# Amplifier_ADC.net
KiCad netlist of a schematic drawn in Altium Designer
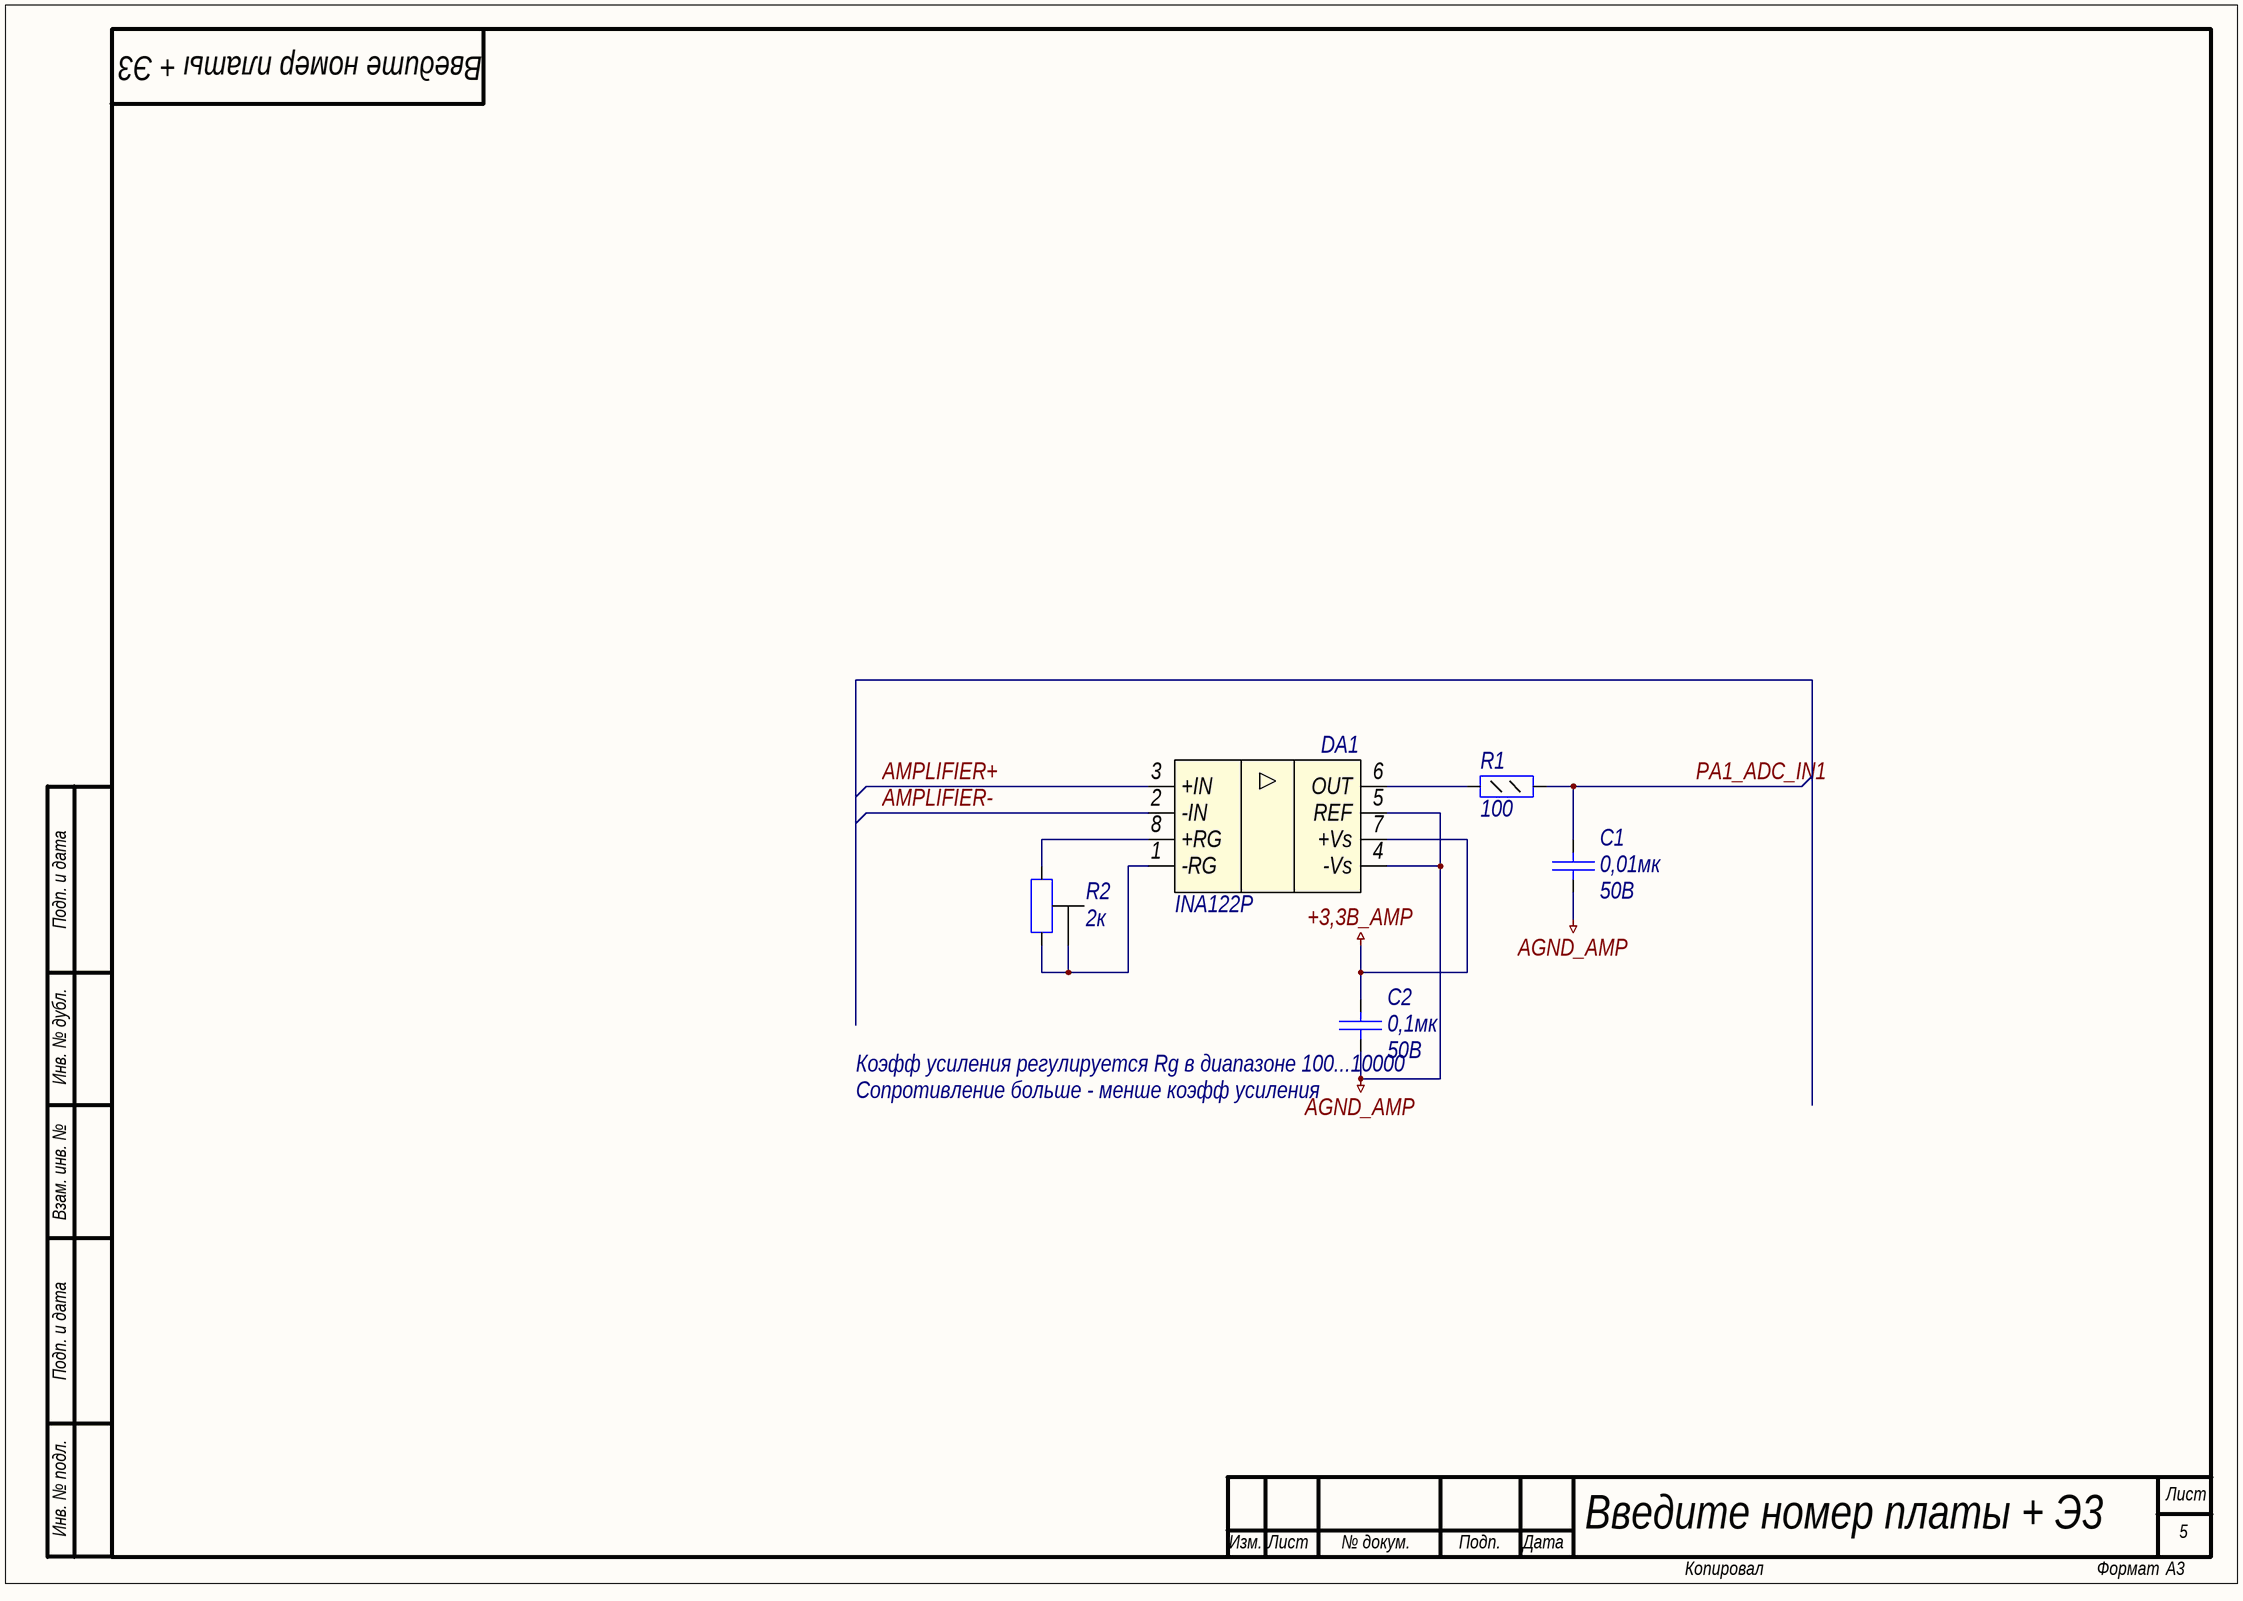
[diagram p0: Amplifier_ADC.SchDoc]

(export (version "E")
  (design (tool "Eeschema 10.0.6"))
  (components
    (comp (ref "C1")
      (value "0,01мк")
      (footprint "C0805")
      (description "Конденсатор")
      (fields
        (field (name "VOLTAGE") "50B")
        (field (name "PART NUMBER") "GRM216R71H103K")
        (field (name "Comment") "Capacitor")
      )
      (libsource (lib "MOP44") (part "Capacitor"))
    )
    (comp (ref "C2")
      (value "0,1мк")
      (footprint "C0805")
      (description "Конденсатор")
      (fields
        (field (name "VOLTAGE") "50В")
        (field (name "PART NUMBER") "GRM21BR71H104KA01L ")
        (field (name "Comment") "Capacitor")
      )
      (libsource (lib "MOP44") (part "Capacitor"))
    )
    (comp (ref "DA1")
      (value "INA122")
      (footprint "DIP8")
      (description "Low Cost Low Power  Instrumentation Amplifier")
      (fields (field (name "PART NUMBER") "INA122P"))
      (libsource (lib "MOP44") (part "INA122"))
    )
    (comp (ref "R1")
      (value "100")
      (footprint "R0805")
      (description "Резистор")
      (fields (field (name "PART NUMBER") "RC0805FR-07100RL") (field (name "POWER") "0,125Вт"))
      (libsource (lib "MOP44") (part "Resistor_0,125Вт"))
    )
    (comp (ref "R2")
      (value "2к")
      (footprint "3296Y")
      (description "Potentiometer")
      (fields (field (name "PART NUMBER") "3296Y-1-202LF") (field (name "POWER") "0,5Вт"))
      (libsource (lib "MOP44") (part "Potentiometer"))
    )
  )
  (nets
    (net (code "1") (name "+3,3В_AMP") (class "Default")
      (node (ref "C2") (pin "2") (pinfunction "2_2") (pintype "passive"))
      (node (ref "DA1") (pin "7") (pinfunction "+Vs_7") (pintype "passive"))
    )
    (net (code "2") (name "/AMPLIFIER+") (class "Default")
      (node (ref "DA1") (pin "3") (pinfunction "+IN_3") (pintype "passive"))
    )
    (net (code "3") (name "/AMPLIFIER-") (class "Default")
      (node (ref "DA1") (pin "2") (pinfunction "-IN_2") (pintype "passive"))
    )
    (net (code "4") (name "/PA1_ADC_IN1") (class "Default")
      (node (ref "C1") (pin "2") (pinfunction "2_2") (pintype "passive"))
      (node (ref "R1") (pin "2") (pinfunction "2_2") (pintype "passive"))
    )
    (net (code "5") (name "AGND_AMP") (class "Default")
      (node (ref "C1") (pin "1") (pinfunction "1_1") (pintype "passive"))
      (node (ref "C2") (pin "1") (pinfunction "1_1") (pintype "passive"))
      (node (ref "DA1") (pin "4") (pinfunction "-Vs_4") (pintype "passive"))
      (node (ref "DA1") (pin "5") (pinfunction "REF_5") (pintype "passive"))
    )
    (net (code "6") (name "Net-(DA1-+RG)") (class "Default")
      (node (ref "DA1") (pin "8") (pinfunction "+RG_8") (pintype "passive"))
      (node (ref "R2") (pin "1") (pinfunction "1_1") (pintype "passive"))
    )
    (net (code "7") (name "Net-(DA1--RG)") (class "Default")
      (node (ref "DA1") (pin "1") (pinfunction "-RG_1") (pintype "passive"))
      (node (ref "R2") (pin "2") (pinfunction "2_2") (pintype "passive"))
      (node (ref "R2") (pin "3") (pinfunction "3_3") (pintype "passive"))
    )
    (net (code "8") (name "Net-(DA1-OUT)") (class "Default")
      (node (ref "DA1") (pin "6") (pinfunction "OUT_6") (pintype "passive"))
      (node (ref "R1") (pin "1") (pinfunction "1_1") (pintype "passive"))
    )
  )
)
